# adc_dac_lo6.net
KiCad netlist of a schematic drawn in Altium Designer
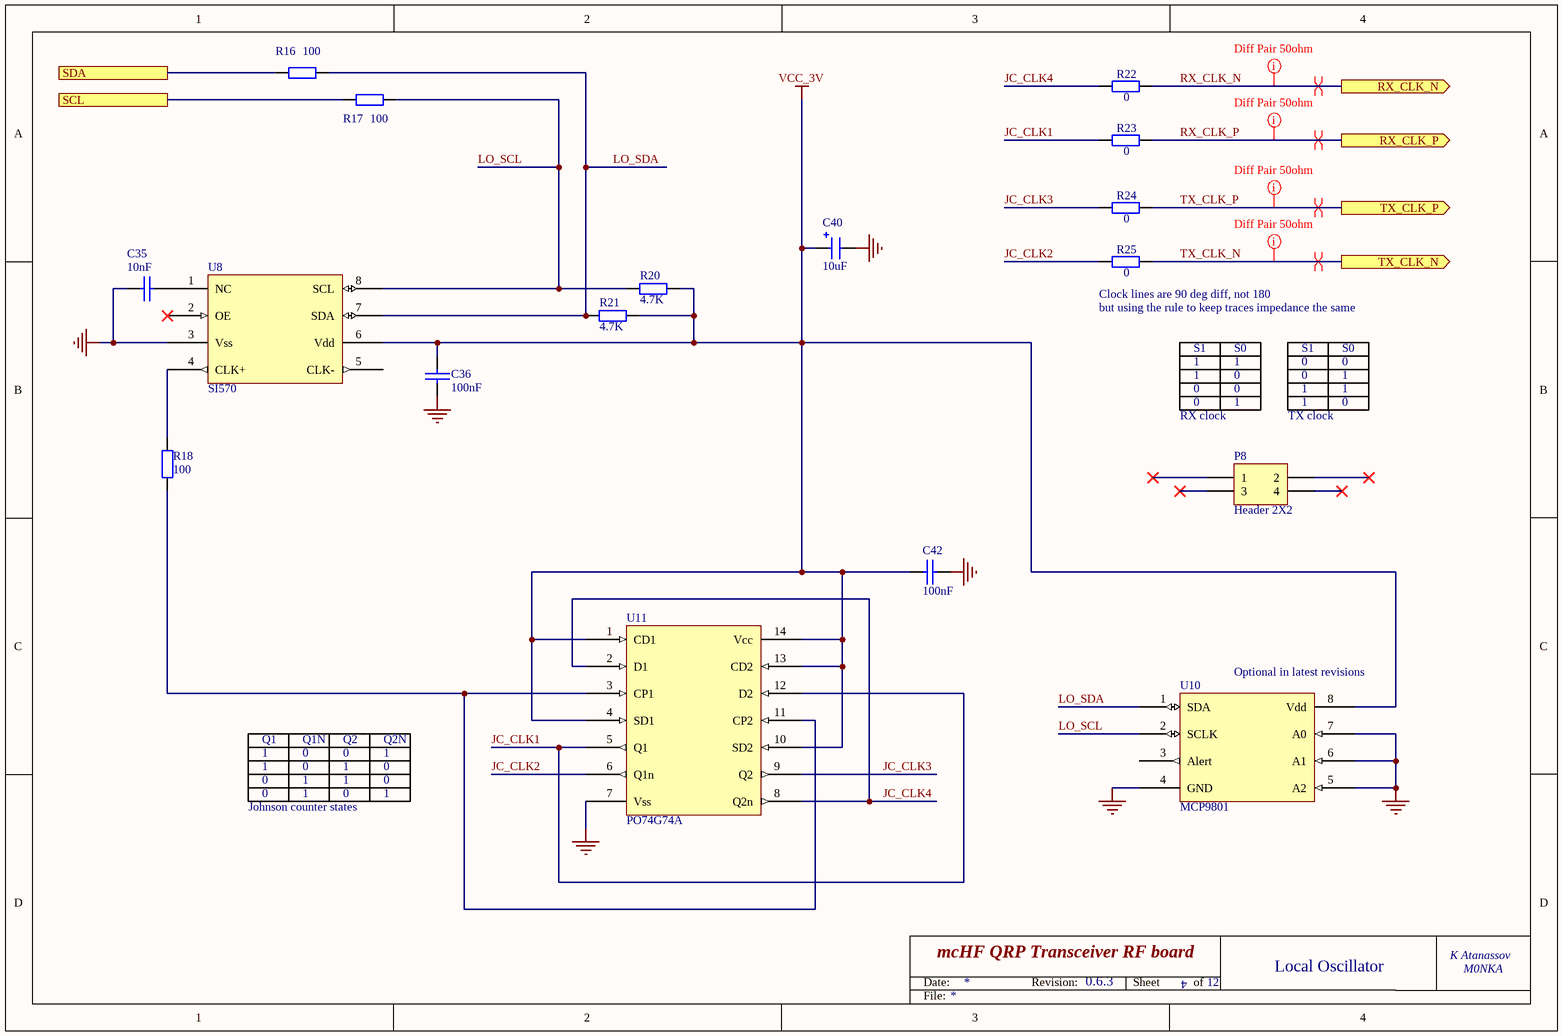
[diagram p0: adc_dac_lo6.SchDoc]

(export (version "E")
  (design (tool "Eeschema 10.0.6"))
  (components
    (comp (ref "C35")
      (value "10nF")
      (footprint "0805-Pro")
      (description "Capacitor")
      (libsource (lib "*") (part "CAP"))
    )
    (comp (ref "C36")
      (value "100nF")
      (footprint "0805-Pro")
      (description "Capacitor")
      (libsource (lib "*") (part "CAP"))
    )
    (comp (ref "C40")
      (value "10uF")
      (footprint "1206_Elec_Cap_N")
      (description "Electrolitic capacitor")
      (libsource (lib "*") (part "CAP-POL"))
    )
    (comp (ref "C42")
      (value "100nF")
      (footprint "0805-Pro")
      (description "Capacitor")
      (libsource (lib "*") (part "CAP"))
    )
    (comp (ref "P8")
      (value "Header 2X2")
      (footprint "HDR2X2")
      (description "Header, 2-Pin, Dual row")
      (fields (field (name "PUBLISHER") "Altium Limited"))
      (libsource (lib "Miscellaneous Connectors") (part "Header 2X2"))
    )
    (comp (ref "R16")
      (value "100")
      (footprint "0805-Pro")
      (description "Resistor")
      (libsource (lib "") (part "RES_2"))
    )
    (comp (ref "R17")
      (value "100")
      (footprint "0805-Pro")
      (description "Resistor")
      (libsource (lib "") (part "RES_2"))
    )
    (comp (ref "R18")
      (value "100")
      (footprint "0805-Pro")
      (description "Resistor")
      (libsource (lib "") (part "RES_1"))
    )
    (comp (ref "R20")
      (value "4.7K")
      (footprint "0805-Pro")
      (description "Resistor")
      (libsource (lib "*") (part "RES"))
    )
    (comp (ref "R21")
      (value "4.7K")
      (footprint "0805-Pro")
      (description "Resistor")
      (libsource (lib "*") (part "RES"))
    )
    (comp (ref "R22")
      (value "0")
      (footprint "0805-Pro")
      (description "Resistor")
      (libsource (lib "mcHF_rf") (part "RES"))
    )
    (comp (ref "R23")
      (value "0")
      (footprint "0805-Pro")
      (description "Resistor")
      (libsource (lib "mcHF_rf") (part "RES"))
    )
    (comp (ref "R24")
      (value "0")
      (footprint "0805-Pro")
      (description "Resistor")
      (libsource (lib "mcHF_rf") (part "RES"))
    )
    (comp (ref "R25")
      (value "0")
      (footprint "0805-Pro")
      (description "Resistor")
      (libsource (lib "mcHF_rf") (part "RES"))
    )
    (comp (ref "U8")
      (value "SI570")
      (footprint "SI570_m")
      (description "I2C programmable XO")
      (libsource (lib "*") (part "SI570"))
    )
    (comp (ref "U10")
      (value "MCP9801")
      (footprint "SO-8")
      (description "2-Wire High-Accuracy Temperature Sensor")
      (libsource (lib "*") (part "MCP9801"))
    )
    (comp (ref "U11")
      (value "PO74G74A")
      (footprint "SO-14-Pro")
      (description "Low Voltage Dual D-Type Positive Edge-Triggered  Flip-Flop with 5V Tolerant Inputs")
      (libsource (lib "*") (part "74LCX74M"))
    )
  )
  (nets
    (net (code "1") (name "/JC_CLK1") (class "Default")
      (node (ref "R23") (pin "2") (pinfunction "2_2") (pintype "passive"))
      (node (ref "U11") (pin "12") (pinfunction "D2_12") (pintype "input"))
      (node (ref "U11") (pin "5") (pinfunction "Q1_5") (pintype "output"))
    )
    (net (code "2") (name "/JC_CLK2") (class "Default")
      (node (ref "R25") (pin "2") (pinfunction "2_2") (pintype "passive"))
      (node (ref "U11") (pin "6") (pinfunction "Q1n_6") (pintype "output"))
    )
    (net (code "3") (name "/JC_CLK3") (class "Default")
      (node (ref "R24") (pin "2") (pinfunction "2_2") (pintype "passive"))
      (node (ref "U11") (pin "9") (pinfunction "Q2_9") (pintype "output"))
    )
    (net (code "4") (name "/JC_CLK4") (class "Default")
      (node (ref "R22") (pin "2") (pinfunction "2_2") (pintype "passive"))
      (node (ref "U11") (pin "2") (pinfunction "D1_2") (pintype "input"))
      (node (ref "U11") (pin "8") (pinfunction "Q2n_8") (pintype "output"))
    )
    (net (code "5") (name "/LO_SCL") (class "Default")
      (node (ref "R17") (pin "1") (pinfunction "1_1") (pintype "passive"))
      (node (ref "R20") (pin "1") (pinfunction "1_1") (pintype "passive"))
      (node (ref "U10") (pin "2") (pinfunction "SCLK_2") (pintype "bidirectional"))
      (node (ref "U8") (pin "8") (pinfunction "SCL_8") (pintype "bidirectional"))
    )
    (net (code "6") (name "/LO_SDA") (class "Default")
      (node (ref "R16") (pin "1") (pinfunction "1_1") (pintype "passive"))
      (node (ref "R21") (pin "1") (pinfunction "1_1") (pintype "passive"))
      (node (ref "U10") (pin "1") (pinfunction "SDA_1") (pintype "bidirectional"))
      (node (ref "U8") (pin "7") (pinfunction "SDA_7") (pintype "bidirectional"))
    )
    (net (code "7") (name "/RX_CLK_N") (class "Default")
      (node (ref "R22") (pin "1") (pinfunction "1_1") (pintype "passive"))
    )
    (net (code "8") (name "/RX_CLK_P") (class "Default")
      (node (ref "R23") (pin "1") (pinfunction "1_1") (pintype "passive"))
    )
    (net (code "9") (name "/SCL") (class "Default")
      (node (ref "R17") (pin "2") (pinfunction "2_2") (pintype "passive"))
    )
    (net (code "10") (name "/SDA") (class "Default")
      (node (ref "R16") (pin "2") (pinfunction "2_2") (pintype "passive"))
    )
    (net (code "11") (name "/TX_CLK_N") (class "Default")
      (node (ref "R25") (pin "1") (pinfunction "1_1") (pintype "passive"))
    )
    (net (code "12") (name "/TX_CLK_P") (class "Default")
      (node (ref "R24") (pin "1") (pinfunction "1_1") (pintype "passive"))
    )
    (net (code "13") (name "GND") (class "Default")
      (node (ref "C35") (pin "1") (pinfunction "1_1") (pintype "passive"))
      (node (ref "C36") (pin "2") (pinfunction "2_2") (pintype "passive"))
      (node (ref "C40") (pin "2") (pinfunction "2_2") (pintype "passive"))
      (node (ref "C42") (pin "1") (pinfunction "1_1") (pintype "passive"))
      (node (ref "U10") (pin "4") (pinfunction "GND_4") (pintype "power_in"))
      (node (ref "U10") (pin "5") (pinfunction "A2_5") (pintype "input"))
      (node (ref "U10") (pin "6") (pinfunction "A1_6") (pintype "input"))
      (node (ref "U10") (pin "7") (pinfunction "A0_7") (pintype "input"))
      (node (ref "U11") (pin "7") (pinfunction "Vss_7") (pintype "power_in"))
      (node (ref "U8") (pin "3") (pinfunction "Vss_3") (pintype "power_in"))
    )
    (net (code "14") (name "Net-(U8-CLK+)") (class "Default")
      (node (ref "R18") (pin "2") (pinfunction "2_2") (pintype "passive"))
      (node (ref "U8") (pin "4") (pinfunction "CLK+_4") (pintype "output"))
    )
    (net (code "15") (name "Net-(U8-NC)") (class "Default")
      (node (ref "C35") (pin "2") (pinfunction "2_2") (pintype "passive"))
      (node (ref "U8") (pin "1") (pinfunction "NC_1") (pintype "passive"))
    )
    (net (code "16") (name "Net-(U11-CP1)") (class "Default")
      (node (ref "R18") (pin "1") (pinfunction "1_1") (pintype "passive"))
      (node (ref "U11") (pin "11") (pinfunction "CP2_11") (pintype "input"))
      (node (ref "U11") (pin "3") (pinfunction "CP1_3") (pintype "input"))
    )
    (net (code "17") (name "VCC_3V") (class "Default")
      (node (ref "C36") (pin "1") (pinfunction "1_1") (pintype "passive"))
      (node (ref "C40") (pin "1") (pinfunction "1_1") (pintype "passive"))
      (node (ref "C42") (pin "2") (pinfunction "2_2") (pintype "passive"))
      (node (ref "R20") (pin "2") (pinfunction "2_2") (pintype "passive"))
      (node (ref "R21") (pin "2") (pinfunction "2_2") (pintype "passive"))
      (node (ref "U10") (pin "8") (pinfunction "Vdd_8") (pintype "power_in"))
      (node (ref "U11") (pin "1") (pinfunction "CD1_1") (pintype "input"))
      (node (ref "U11") (pin "10") (pinfunction "SD2_10") (pintype "input"))
      (node (ref "U11") (pin "13") (pinfunction "CD2_13") (pintype "input"))
      (node (ref "U11") (pin "14") (pinfunction "Vcc_14") (pintype "power_in"))
      (node (ref "U11") (pin "4") (pinfunction "SD1_4") (pintype "input"))
      (node (ref "U8") (pin "6") (pinfunction "Vdd_6") (pintype "power_in"))
    )
    (net (code "18") (name "unconnected-(P8-Pad1)") (class "Default")
      (node (ref "P8") (pin "1") (pinfunction "1_1") (pintype "passive+no_connect"))
    )
    (net (code "19") (name "unconnected-(P8-Pad2)") (class "Default")
      (node (ref "P8") (pin "2") (pinfunction "2_2") (pintype "passive+no_connect"))
    )
    (net (code "20") (name "unconnected-(P8-Pad3)") (class "Default")
      (node (ref "P8") (pin "3") (pinfunction "3_3") (pintype "passive+no_connect"))
    )
    (net (code "21") (name "unconnected-(P8-Pad4)") (class "Default")
      (node (ref "P8") (pin "4") (pinfunction "4_4") (pintype "passive+no_connect"))
    )
    (net (code "22") (name "unconnected-(U8-CLK--Pad5)") (class "Default")
      (node (ref "U8") (pin "5") (pinfunction "CLK-_5") (pintype "output"))
    )
    (net (code "23") (name "unconnected-(U8-OE-Pad2)") (class "Default")
      (node (ref "U8") (pin "2") (pinfunction "OE_2") (pintype "input+no_connect"))
    )
    (net (code "24") (name "unconnected-(U10-Alert-Pad3)") (class "Default")
      (node (ref "U10") (pin "3") (pinfunction "Alert_3") (pintype "output"))
    )
  )
)
